# PULSE.net
KiCad netlist of a schematic drawn in Altium Designer
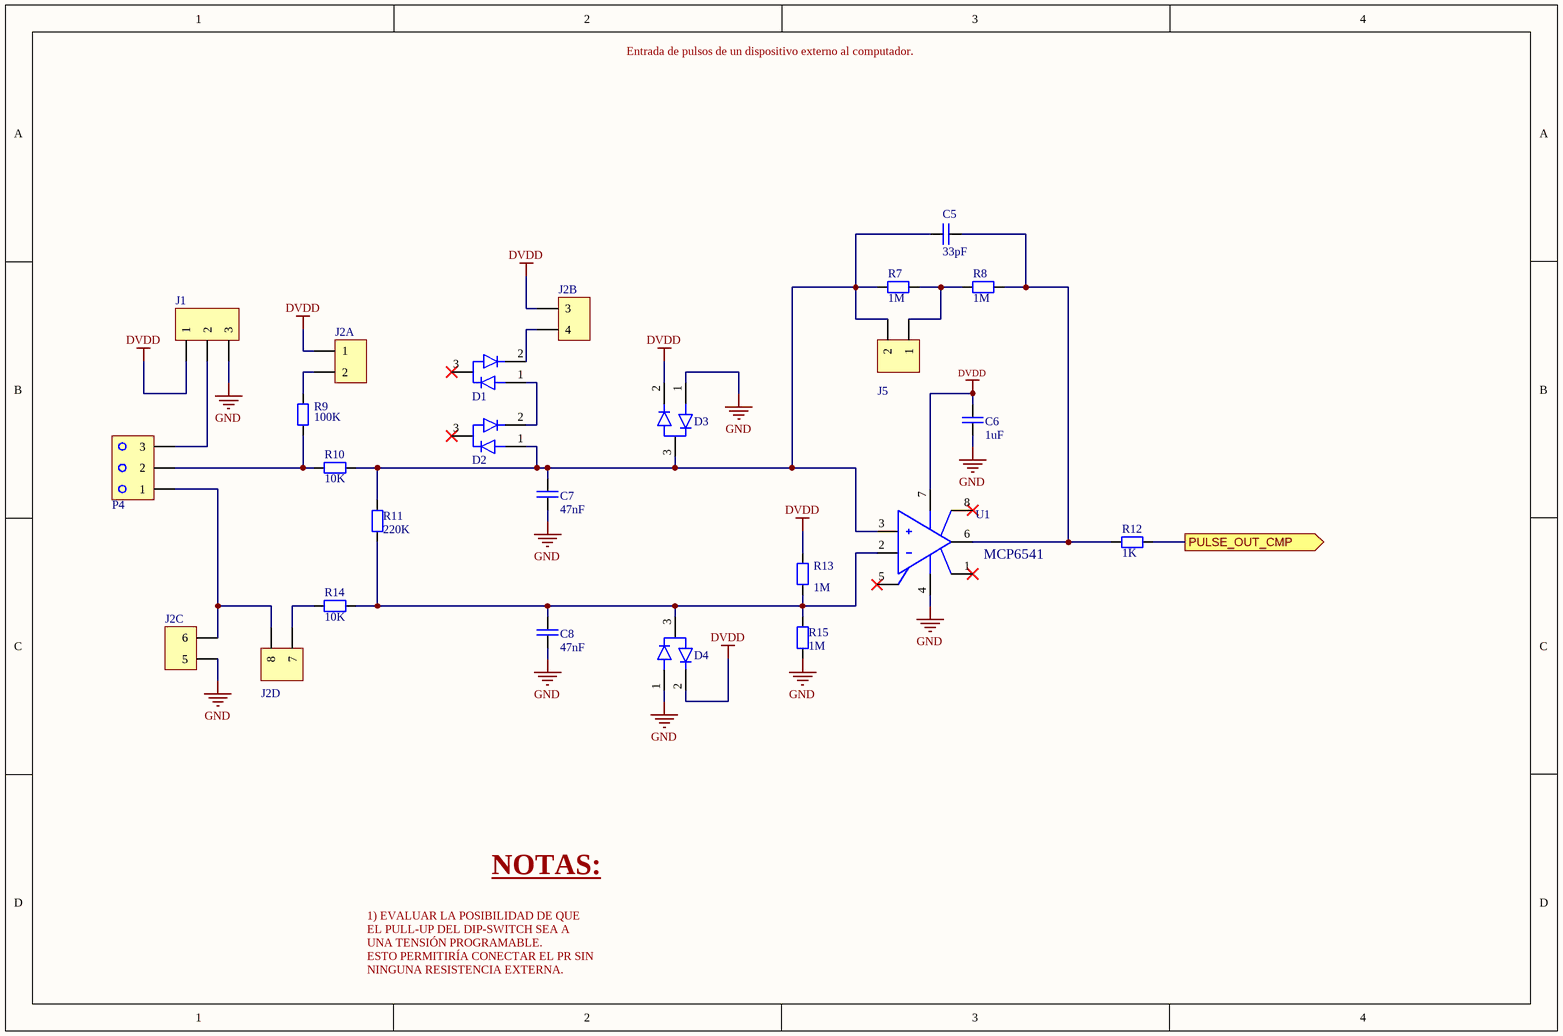
[diagram p0: PULSE.SchDoc]

(export (version "E")
  (design (tool "Eeschema 10.0.6"))
  (components
    (comp (ref "C5")
      (value "33pF")
      (footprint "CAP_SM0805_YAGEOCC2_N")
      (description "CAP 33pF SM0805 NPO 50V YAGEO CC2")
      (fields
        (field (name "MANUFACTURER") "Yageo")
        (field (name "MANUFACTURER PART NUMBER") "CC0805JRNPO9BN330")
      )
      (libsource (lib "Yageo") (part "CC0805JRNPO9BN330"))
    )
    (comp (ref "C6")
      (value "1uF")
      (footprint "CAP_SM0805_YAGEOCC2_N")
      (description "CAP 1uF SM0805 X7R 25V YAGEO CC2")
      (fields
        (field (name "MANUFACTURER") "Yageo")
        (field (name "MANUFACTURER PART NUMBER") "CC0805KKX7R8BB105")
      )
      (libsource (lib "Yageo") (part "CC0805KKX7R8BB105"))
    )
    (comp (ref "C7")
      (value "47nF")
      (footprint "CAP_SM0805_YAGEOCC2_N")
      (description "CAP 47nF SM0805 X7R 25V YAGEO CC2")
      (fields
        (field (name "MANUFACTURER") "Yageo")
        (field (name "MANUFACTURER PART NUMBER") "CC0805KRX7R8BB473")
      )
      (libsource (lib "Yageo") (part "CC0805KRX7R8BB473"))
    )
    (comp (ref "C8")
      (value "47nF")
      (footprint "CAP_SM0805_YAGEOCC2_N")
      (description "CAP 47nF SM0805 X7R 25V YAGEO CC2")
      (fields
        (field (name "MANUFACTURER") "Yageo")
        (field (name "MANUFACTURER PART NUMBER") "CC0805KRX7R8BB473")
      )
      (libsource (lib "Yageo") (part "CC0805KRX7R8BB473"))
    )
    (comp (ref "D1")
      (value "BAV23S")
      (footprint "BAV23S")
      (description "DIODE ARRAY GP 250V 200MA SOT23")
      (fields (field (name "MANUFACTURER") "onsemi"))
      (libsource (lib "diode") (part "BAV23S"))
    )
    (comp (ref "D2")
      (value "BAV23S")
      (footprint "BAV23S")
      (description "DIODE ARRAY GP 250V 200MA SOT23")
      (fields (field (name "MANUFACTURER") "onsemi"))
      (libsource (lib "diode") (part "BAV23S"))
    )
    (comp (ref "D3")
      (value "BAV23S")
      (footprint "BAV23S")
      (description "DIODE ARRAY GP 250V 200MA SOT23")
      (fields (field (name "MANUFACTURER") "onsemi"))
      (libsource (lib "diode") (part "BAV23S"))
    )
    (comp (ref "D4")
      (value "BAV23S")
      (footprint "BAV23S")
      (description "DIODE ARRAY GP 250V 200MA SOT23")
      (fields (field (name "MANUFACTURER") "onsemi"))
      (libsource (lib "diode") (part "BAV23S"))
    )
    (comp (ref "J1")
      (value "~")
      (footprint "HEADER PIN 1X3")
      (description "1 x 3 - Cuttable - true hole  2.54mm - Pb free")
      (fields
        (field (name "MANUFACTURER") "Amphenol ICC")
        (field (name "MANUFACTURER PART NUMBER") "54101-T06-00")
      )
      (libsource (lib "header_pin") (part "54101-T0600LF-03"))
    )
    (comp (ref "J2")
      (value "Usar equivalente")
      (footprint "HEADER PIN 2X4")
      (description "2 x 4  - true hole  2.54mm")
      (fields
        (field (name "MANUFACTURER") "Amphenol ICC")
        (field (name "MANUFACTURER PART NUMBER") "54102-T0604LF")
      )
      (libsource (lib "header_pin") (part "54102-T0604LF-JUMPER"))
    )
    (comp (ref "J5")
      (value "Usar Equivalente")
      (footprint "HEADER PIN 1X2")
      (description "1 x 2 - true hole  2.54mm - Pb free")
      (fields
        (field (name "MANUFACTURER") "Amphenol ICC")
        (field (name "MANUFACTURER PART NUMBER") "54101-T0600LF")
      )
      (libsource (lib "header_pin") (part "54101-T0600LF-CUT-2"))
    )
    (comp (ref "P4")
      (value "WJ15EDGVC-3.81-3P")
      (footprint "HEADER PLUG 3")
      (description "TERM BLOK FEMALE 1X3 3.81MM")
      (fields (field (name "MANUFACTURER") "Ningbo Kangnex Elec"))
      (libsource (lib "plug") (part "WJ15EDGVC-3.81-3P"))
    )
    (comp (ref "R7")
      (value "1M")
      (footprint "RES_SM0805_YAGEORC_N")
      (description "RES 1M SM0805 YAGEO RC_L")
      (fields
        (field (name "MANUFACTURER") "Yageo")
        (field (name "MANUFACTURER PART NUMBER") "RC0805FR-071ML")
      )
      (libsource (lib "Yageo") (part "RC0805FR-071ML"))
    )
    (comp (ref "R8")
      (value "1M")
      (footprint "RES_SM0805_YAGEORC_N")
      (description "RES 1M SM0805 YAGEO RC_L")
      (fields
        (field (name "MANUFACTURER") "Yageo")
        (field (name "MANUFACTURER PART NUMBER") "RC0805FR-071ML")
      )
      (libsource (lib "Yageo") (part "RC0805FR-071ML"))
    )
    (comp (ref "R9")
      (value "100K")
      (footprint "RES_SM0805_YAGEORC_N")
      (description "RES 100K SM0805 YAGEO RC_L")
      (fields
        (field (name "MANUFACTURER") "Yageo")
        (field (name "MANUFACTURER PART NUMBER") "RC0805FR-07100KL")
      )
      (libsource (lib "Yageo") (part "RC0805FR-07100KL"))
    )
    (comp (ref "R10")
      (value "10K")
      (footprint "RES_SM0805_YAGEORC_N")
      (description "RES 10K SM0805 YAGEO RC_L")
      (fields
        (field (name "MANUFACTURER") "Yageo")
        (field (name "MANUFACTURER PART NUMBER") "RC0805FR-0710KL")
      )
      (libsource (lib "Yageo") (part "RC0805FR-0710KL"))
    )
    (comp (ref "R11")
      (value "220K")
      (footprint "RES_SM0805_YAGEORC_N")
      (description "RES 220K SM0805 YAGEO RC_L")
      (fields
        (field (name "MANUFACTURER") "Yageo")
        (field (name "MANUFACTURER PART NUMBER") "RC0805FR-07220KL")
      )
      (libsource (lib "Yageo") (part "RC0805FR-07220KL"))
    )
    (comp (ref "R12")
      (value "1K")
      (footprint "RES_SM0805_YAGEORC_N")
      (description "RES 1K SM0805 YAGEO RC_L")
      (fields
        (field (name "MANUFACTURER") "Yageo")
        (field (name "MANUFACTURER PART NUMBER") "RC0805FR-071KL")
      )
      (libsource (lib "Yageo") (part "RC0805FR-071KL"))
    )
    (comp (ref "R13")
      (value "1M")
      (footprint "RES_SM0805_YAGEORC_N")
      (description "RES 1M SM0805 YAGEO RC_L")
      (fields
        (field (name "MANUFACTURER") "Yageo")
        (field (name "MANUFACTURER PART NUMBER") "RC0805FR-071ML")
      )
      (libsource (lib "") (part "RC0805FR-071ML_1"))
    )
    (comp (ref "R14")
      (value "10K")
      (footprint "RES_SM0805_YAGEORC_N")
      (description "RES 10K SM0805 YAGEO RC_L")
      (fields
        (field (name "MANUFACTURER") "Yageo")
        (field (name "MANUFACTURER PART NUMBER") "RC0805FR-0710KL")
      )
      (libsource (lib "Yageo") (part "RC0805FR-0710KL"))
    )
    (comp (ref "R15")
      (value "1M")
      (footprint "RES_SM0805_YAGEORC_N")
      (description "RES 1M SM0805 YAGEO RC_L")
      (fields
        (field (name "MANUFACTURER") "Yageo")
        (field (name "MANUFACTURER PART NUMBER") "RC0805FR-071ML")
      )
      (libsource (lib "") (part "RC0805FR-071ML_1"))
    )
    (comp (ref "U1")
      (value "MCP6541")
      (footprint "MCP6541-E/SN")
      (description "IC COMP PP I/O SNGL 1.6V 8SOIC")
      (fields
        (field (name "MANUFACTURER") "Microchip Tech")
        (field (name "MANUFACTURER PART NUMBER") "MCP6541-E/SN")
      )
      (libsource (lib "OP_Amps") (part "MCP6541-E/SN"))
    )
  )
  (nets
    (net (code "1") (name "/PULSE_OUT_CMP") (class "Default")
      (node (ref "R12") (pin "2") (pintype "passive"))
    )
    (net (code "2") (name "DVDD") (class "Default")
      (node (ref "C6") (pin "1") (pintype "passive"))
      (node (ref "D3") (pin "2") (pinfunction "2_2") (pintype "passive"))
      (node (ref "D4") (pin "2") (pinfunction "2_2") (pintype "passive"))
      (node (ref "J1") (pin "1") (pinfunction "1_1") (pintype "passive"))
      (node (ref "J2") (pin "1") (pinfunction "1_1") (pintype "passive"))
      (node (ref "J2") (pin "3") (pinfunction "3_3") (pintype "passive"))
      (node (ref "R13") (pin "2") (pintype "passive"))
      (node (ref "U1") (pin "7") (pinfunction "V+_7") (pintype "power_in"))
    )
    (net (code "3") (name "GND") (class "Default")
      (node (ref "C6") (pin "2") (pintype "passive"))
      (node (ref "C7") (pin "2") (pintype "passive"))
      (node (ref "C8") (pin "2") (pintype "passive"))
      (node (ref "D3") (pin "1") (pinfunction "1_1") (pintype "passive"))
      (node (ref "D4") (pin "1") (pinfunction "1_1") (pintype "passive"))
      (node (ref "J1") (pin "3") (pinfunction "3_3") (pintype "passive"))
      (node (ref "J2") (pin "5") (pinfunction "5_5") (pintype "passive"))
      (node (ref "R15") (pin "1") (pintype "passive"))
      (node (ref "U1") (pin "4") (pinfunction "V-_4") (pintype "power_in"))
    )
    (net (code "4") (name "Net-(D1-Pad1)") (class "Default")
      (node (ref "D1") (pin "1") (pinfunction "1_1") (pintype "passive"))
      (node (ref "D2") (pin "2") (pinfunction "2_2") (pintype "passive"))
    )
    (net (code "5") (name "Net-(D1-Pad2)") (class "Default")
      (node (ref "D1") (pin "2") (pinfunction "2_2") (pintype "passive"))
      (node (ref "J2") (pin "4") (pinfunction "4_4") (pintype "passive"))
    )
    (net (code "6") (name "Net-(J1-Pad2)") (class "Default")
      (node (ref "J1") (pin "2") (pinfunction "2_2") (pintype "passive"))
      (node (ref "P4") (pin "3") (pinfunction "3_3") (pintype "passive"))
    )
    (net (code "7") (name "Net-(J2-Pad2)") (class "Default")
      (node (ref "J2") (pin "2") (pinfunction "2_2") (pintype "passive"))
      (node (ref "R9") (pin "2") (pintype "passive"))
    )
    (net (code "8") (name "Net-(J2-Pad6)") (class "Default")
      (node (ref "J2") (pin "6") (pinfunction "6_6") (pintype "passive"))
      (node (ref "J2") (pin "8") (pinfunction "8_8") (pintype "passive"))
      (node (ref "P4") (pin "1") (pinfunction "1_1") (pintype "passive"))
    )
    (net (code "9") (name "Net-(J2-Pad7)") (class "Default")
      (node (ref "J2") (pin "7") (pinfunction "7_7") (pintype "passive"))
      (node (ref "R14") (pin "1") (pintype "passive"))
    )
    (net (code "10") (name "Net-(J5-Pad1)") (class "Default")
      (node (ref "J5") (pin "1") (pinfunction "1_1") (pintype "passive"))
      (node (ref "R7") (pin "2") (pintype "passive"))
      (node (ref "R8") (pin "1") (pintype "passive"))
    )
    (net (code "11") (name "Net-(P4-Pad2)") (class "Default")
      (node (ref "P4") (pin "2") (pinfunction "2_2") (pintype "passive"))
      (node (ref "R10") (pin "1") (pintype "passive"))
      (node (ref "R9") (pin "1") (pintype "passive"))
    )
    (net (code "12") (name "Net-(U1-IN+)") (class "Default")
      (node (ref "C5") (pin "1") (pintype "passive"))
      (node (ref "C7") (pin "1") (pintype "passive"))
      (node (ref "D2") (pin "1") (pinfunction "1_1") (pintype "passive"))
      (node (ref "D3") (pin "3") (pinfunction "3_3") (pintype "passive"))
      (node (ref "J5") (pin "2") (pinfunction "2_2") (pintype "passive"))
      (node (ref "R10") (pin "2") (pintype "passive"))
      (node (ref "R11") (pin "2") (pintype "passive"))
      (node (ref "R7") (pin "1") (pintype "passive"))
      (node (ref "U1") (pin "3") (pinfunction "IN+_3") (pintype "passive"))
    )
    (net (code "13") (name "Net-(U1-IN-)") (class "Default")
      (node (ref "C8") (pin "1") (pintype "passive"))
      (node (ref "D4") (pin "3") (pinfunction "3_3") (pintype "passive"))
      (node (ref "R11") (pin "1") (pintype "passive"))
      (node (ref "R13") (pin "1") (pintype "passive"))
      (node (ref "R14") (pin "2") (pintype "passive"))
      (node (ref "R15") (pin "2") (pintype "passive"))
      (node (ref "U1") (pin "2") (pinfunction "IN-_2") (pintype "passive"))
    )
    (net (code "14") (name "Net-(U1-OUT)") (class "Default")
      (node (ref "C5") (pin "2") (pintype "passive"))
      (node (ref "R12") (pin "1") (pintype "passive"))
      (node (ref "R8") (pin "2") (pintype "passive"))
      (node (ref "U1") (pin "6") (pinfunction "OUT_6") (pintype "passive"))
    )
    (net (code "15") (name "unconnected-(D1-Pad3)") (class "Default")
      (node (ref "D1") (pin "3") (pinfunction "3_3") (pintype "passive+no_connect"))
    )
    (net (code "16") (name "unconnected-(D2-Pad3)") (class "Default")
      (node (ref "D2") (pin "3") (pinfunction "3_3") (pintype "passive+no_connect"))
    )
    (net (code "17") (name "unconnected-(U1-OS_NUL-Pad1)") (class "Default")
      (node (ref "U1") (pin "1") (pinfunction "OS_NUL_1") (pintype "passive+no_connect"))
    )
    (net (code "18") (name "unconnected-(U1-OS_NUL-Pad5)") (class "Default")
      (node (ref "U1") (pin "5") (pinfunction "OS_NUL_5") (pintype "passive+no_connect"))
    )
    (net (code "19") (name "unconnected-(U1-TAB-Pad8)") (class "Default")
      (node (ref "U1") (pin "8") (pinfunction "TAB_8") (pintype "passive+no_connect"))
    )
  )
)
